# CH32F_V208W-R0.net
KiCad netlist of a schematic drawn in Altium Designer
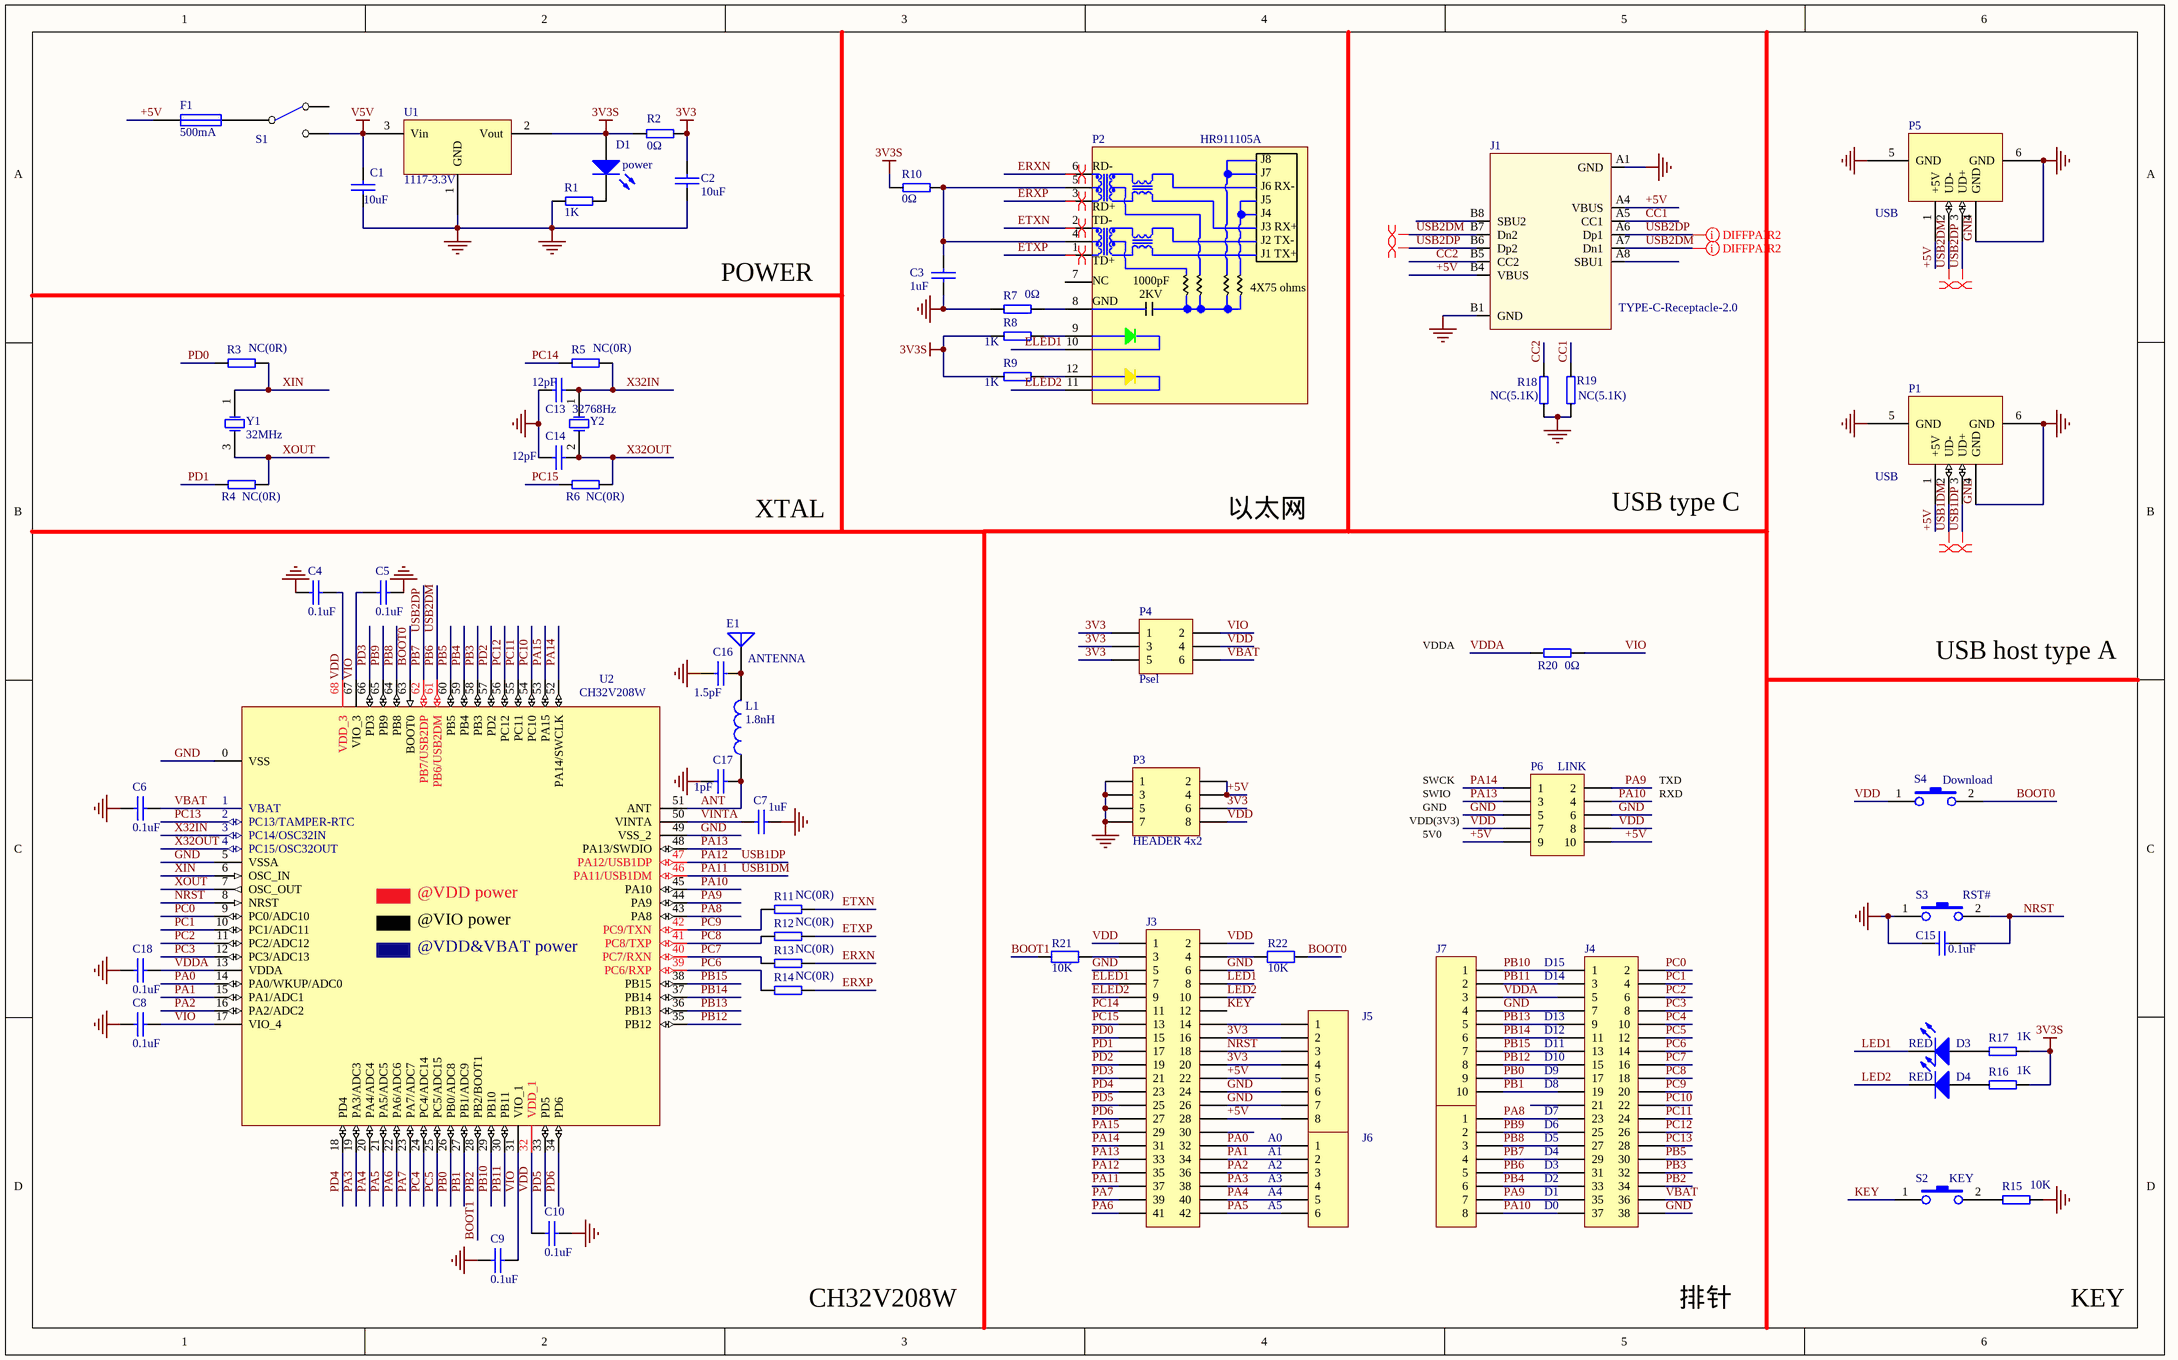
[diagram p0: CH32F&V208W-R0.SchDoc]

(export (version "E")
  (design (tool "Eeschema 10.0.6"))
  (components
    (comp (ref "C1")
      (value "10uF")
      (footprint "3216_C")
      (description "Capacitor")
      (libsource (lib "") (part "CAP_1"))
    )
    (comp (ref "C2")
      (value "10uF")
      (footprint "0603_C")
      (description "Capacitor")
      (libsource (lib "") (part "CAP_1"))
    )
    (comp (ref "C3")
      (value "1uF")
      (footprint "0603_C")
      (description "Capacitor")
      (libsource (lib "") (part "CAP_1"))
    )
    (comp (ref "C4")
      (value "0.1uF")
      (footprint "0603_C")
      (description "Capacitor")
      (libsource (lib "*") (part "CAP"))
    )
    (comp (ref "C5")
      (value "0.1uF")
      (footprint "0603_C")
      (description "Capacitor")
      (libsource (lib "*") (part "CAP"))
    )
    (comp (ref "C6")
      (value "0.1uF")
      (footprint "0603_C")
      (description "Capacitor")
      (libsource (lib "*") (part "CAP"))
    )
    (comp (ref "C7")
      (value "1uF")
      (footprint "0603_C")
      (description "Capacitor")
      (libsource (lib "*") (part "CAP"))
    )
    (comp (ref "C8")
      (value "0.1uF")
      (footprint "0603_C")
      (description "Capacitor")
      (libsource (lib "*") (part "CAP"))
    )
    (comp (ref "C9")
      (value "0.1uF")
      (footprint "0603_C")
      (description "Capacitor")
      (libsource (lib "*") (part "CAP"))
    )
    (comp (ref "C10")
      (value "0.1uF")
      (footprint "0603_C")
      (description "Capacitor")
      (libsource (lib "*") (part "CAP"))
    )
    (comp (ref "C13")
      (value "12pF")
      (footprint "0603_C")
      (description "Capacitor")
      (libsource (lib "") (part "CAP_1"))
    )
    (comp (ref "C14")
      (value "12pF")
      (footprint "0603_C")
      (description "Capacitor")
      (libsource (lib "") (part "CAP_1"))
    )
    (comp (ref "C15")
      (value "0.1uF")
      (footprint "0603_C")
      (description "Capacitor")
      (libsource (lib "*") (part "CAP"))
    )
    (comp (ref "C16")
      (value "1.5pF")
      (footprint "0603_C")
      (description "Capacitor")
      (libsource (lib "*") (part "CAP"))
    )
    (comp (ref "C17")
      (value "1pF")
      (footprint "0603_C")
      (description "Capacitor")
      (libsource (lib "*") (part "CAP"))
    )
    (comp (ref "C18")
      (value "0.1uF")
      (footprint "0603_C")
      (description "Capacitor")
      (libsource (lib "*") (part "CAP"))
    )
    (comp (ref "D1")
      (value "power")
      (footprint "0603+")
      (description "Typical INFRARED GaAs LED")
      (fields (field (name "PUBLISHER") "Altium Limited"))
      (libsource (lib "*") (part "LED0"))
    )
    (comp (ref "D3")
      (value "RED")
      (footprint "0603+")
      (description "Typical INFRARED GaAs LED")
      (fields (field (name "PUBLISHER") "Altium Limited"))
      (libsource (lib "*") (part "LED0"))
    )
    (comp (ref "D4")
      (value "RED")
      (footprint "0603+")
      (description "Typical INFRARED GaAs LED")
      (fields (field (name "PUBLISHER") "Altium Limited"))
      (libsource (lib "*") (part "LED0"))
    )
    (comp (ref "E1")
      (value "ANTENNA")
      (footprint "MYPCB:ANT-F-1-2.4G-1.6")
      (description "Generic Antenna")
      (libsource (lib "*") (part "ANTENNA"))
    )
    (comp (ref "F1")
      (value "500mA")
      (footprint "0603")
      (description "Fuse")
      (libsource (lib "wch_sch_others") (part "FUSE1"))
    )
    (comp (ref "J1")
      (value "TYPE-C-Receptacle-2.0")
      (footprint "TYPE-C-Receptacle-2.0")
      (description "Type-C USB2.0 母座")
      (libsource (lib "Miscellaneous SCH Lib") (part "TYPE-C-Receptacle-2.0"))
    )
    (comp (ref "J3")
      (value "Header 21X2")
      (footprint "IDC42-2.54mm")
      (description "Header, 21-Pin, Dual row")
      (fields (field (name "PUBLISHER") "Altium Limited"))
      (libsource (lib "PCB_Project") (part "Header 21X2"))
    )
    (comp (ref "J4")
      (value "Header 19X2")
      (footprint "IDC38-2.54mm")
      (description "Header, 19-Pin, Dual row")
      (fields (field (name "PUBLISHER") "Altium Limited"))
      (libsource (lib "Miscellaneous Connectors") (part "Header 19X2"))
    )
    (comp (ref "J5")
      (value "Header 8")
      (footprint "SIP8-2.54mm")
      (description "Header, 8-Pin")
      (fields (field (name "PUBLISHER") "Altium Limited"))
      (libsource (lib "Miscellaneous Connectors") (part "Header 8"))
    )
    (comp (ref "J6")
      (value "Header 6")
      (footprint "SIP6-2.54MM")
      (description "Header, 6-Pin")
      (fields (field (name "PUBLISHER") "Altium Limited"))
      (libsource (lib "Miscellaneous Connectors") (part "Header 6"))
    )
    (comp (ref "J7")
      (value "Header 10")
      (footprint "SIP10-2.54mm")
      (description "Header, 10-Pin")
      (fields (field (name "PUBLISHER") "Altium Limited"))
      (libsource (lib "Miscellaneous Connectors") (part "Header 10"))
    )
    (comp (ref "J8")
      (value "Header 8")
      (footprint "SIP8-2.54mm")
      (description "Header, 8-Pin")
      (fields (field (name "PUBLISHER") "Altium Limited"))
      (libsource (lib "") (part "Header 8_1"))
    )
    (comp (ref "L1") (value "1.8nH") (footprint "0603") (libsource (lib "*") (part "INDUCTOR")))
    (comp (ref "P1")
      (value "USB")
      (footprint "USBAF")
      (description "USB Port")
      (libsource (lib "*") (part "USB"))
    )
    (comp (ref "P2") (value "HR911105A") (footprint "HR911105A") (libsource (lib "*") (part "HR911105A")))
    (comp (ref "P3")
      (value "HEADER 4x2")
      (footprint "MYPCB:IDC8-2.54mm")
      (description "Header, 4-Pin, Dual row")
      (libsource (lib "wch_sch_others") (part "HEADER 4x2"))
    )
    (comp (ref "P4")
      (value "Psel")
      (footprint "IDC6-2.54mm")
      (description "Header, 3-Pin, Dual row, Right Angle")
      (fields (field (name "PUBLISHER") "Altium Limited"))
      (libsource (lib "Miscellaneous Connectors") (part "Header 3X2H"))
    )
    (comp (ref "P5")
      (value "USB")
      (footprint "USBAF")
      (description "USB Port")
      (libsource (lib "*") (part "USB"))
    )
    (comp (ref "P6")
      (value "LINK")
      (footprint "IDC10-2.54mm")
      (description "Header, 5-Pin, Dual row, Right Angle")
      (fields (field (name "PUBLISHER") "Altium Limited"))
      (libsource (lib "Miscellaneous Connectors") (part "Header 5X2H"))
    )
    (comp (ref "R1") (value "1K") (footprint "0603") (libsource (lib "wch_sch_others") (part "RES")))
    (comp (ref "R2") (value "0Ω") (footprint "0603") (libsource (lib "wch_sch_others") (part "RES")))
    (comp (ref "R3") (value "NC(0R)") (footprint "0603") (libsource (lib "wch_sch_others") (part "RES")))
    (comp (ref "R4") (value "NC(0R)") (footprint "0603") (libsource (lib "wch_sch_others") (part "RES")))
    (comp (ref "R5") (value "NC(0R)") (footprint "0603") (libsource (lib "wch_sch_others") (part "RES")))
    (comp (ref "R6") (value "NC(0R)") (footprint "0603") (libsource (lib "wch_sch_others") (part "RES")))
    (comp (ref "R7") (value "0Ω") (footprint "0603") (libsource (lib "wch_sch_others") (part "RES")))
    (comp (ref "R8") (value "1K") (footprint "0603") (libsource (lib "wch_sch_others") (part "RES")))
    (comp (ref "R9") (value "1K") (footprint "0603") (libsource (lib "wch_sch_others") (part "RES")))
    (comp (ref "R10") (value "0Ω") (footprint "0603") (libsource (lib "wch_sch_others") (part "RES")))
    (comp (ref "R11") (value "NC(0R)") (footprint "0603") (libsource (lib "wch_sch_others") (part "RES")))
    (comp (ref "R12") (value "NC(0R)") (footprint "0603") (libsource (lib "wch_sch_others") (part "RES")))
    (comp (ref "R13") (value "NC(0R)") (footprint "0603") (libsource (lib "wch_sch_others") (part "RES")))
    (comp (ref "R14") (value "NC(0R)") (footprint "0603") (libsource (lib "wch_sch_others") (part "RES")))
    (comp (ref "R15") (value "10K") (footprint "0603") (libsource (lib "wch_sch_others") (part "RES")))
    (comp (ref "R16") (value "1K") (footprint "0603") (libsource (lib "wch_sch_others") (part "RES")))
    (comp (ref "R17") (value "1K") (footprint "0603") (libsource (lib "wch_sch_others") (part "RES")))
    (comp (ref "R18") (value "NC(5.1K)") (footprint "0603") (libsource (lib "wch_sch_others") (part "RES")))
    (comp (ref "R19") (value "NC(5.1K)") (footprint "0603") (libsource (lib "wch_sch_others") (part "RES")))
    (comp (ref "R20") (value "0Ω") (footprint "0603") (libsource (lib "*") (part "R")))
    (comp (ref "R21")
      (value "10K")
      (footprint "0603")
      (description "Resistor")
      (libsource (lib "Miscellaneous Devices") (part "Res2"))
    )
    (comp (ref "R22")
      (value "10K")
      (footprint "0603")
      (description "Resistor")
      (libsource (lib "Miscellaneous Devices") (part "Res2"))
    )
    (comp (ref "S1") (value "SW SPDT") (footprint "KEY_B") (libsource (lib "*") (part "SW SPDT")))
    (comp (ref "S2")
      (value "KEY")
      (footprint "SMD_6.1x3.65x2.5mm-KEY")
      (libsource (lib "wch_sch_others") (part "KEY1"))
    )
    (comp (ref "S3")
      (value "RST#")
      (footprint "SMD_6.1x3.65x2.5mm-KEY")
      (libsource (lib "wch_sch_others") (part "KEY1"))
    )
    (comp (ref "S4")
      (value "Download")
      (footprint "SMD_6.1x3.65x2.5mm-KEY")
      (libsource (lib "wch_sch_others") (part "KEY1"))
    )
    (comp (ref "U1")
      (value "1117-3.3V")
      (footprint "SOT-223")
      (libsource (lib "wch_sch_others") (part "1117-3.3V"))
    )
    (comp (ref "U2")
      (value "CH32V208W")
      (footprint "QFN68_8x8")
      (description "RISC-V BLE5.3 MCU, 10M Ethernet, 2*USB, CAN")
      (libsource (lib "CHXXX") (part "CH32V208W"))
    )
    (comp (ref "Y1")
      (value "32MHz")
      (footprint "XT3225")
      (description "Crystal Oscillator")
      (fields (field (name "PUBLISHER") "Altium Limited"))
      (libsource (lib "*") (part "XTAL"))
    )
    (comp (ref "Y2")
      (value "32768Hz")
      (footprint "FC-135")
      (description "Crystal Oscillator")
      (fields (field (name "PUBLISHER") "Altium Limited"))
      (libsource (lib "") (part "XTAL_1"))
    )
  )
  (nets
    (net (code "1") (name "/+5V") (class "Default")
      (node (ref "F1") (pin "1") (pinfunction "1_1") (pintype "passive"))
      (node (ref "J1") (pin "A4") (pinfunction "VBUS_A4") (pintype "passive"))
      (node (ref "J1") (pin "B4") (pinfunction "VBUS_B4") (pintype "passive"))
      (node (ref "J3") (pin "22") (pinfunction "22_22") (pintype "passive"))
      (node (ref "J3") (pin "28") (pinfunction "28_28") (pintype "passive"))
      (node (ref "J5") (pin "5") (pinfunction "5_5") (pintype "passive"))
      (node (ref "J5") (pin "8") (pinfunction "8_8") (pintype "passive"))
      (node (ref "P1") (pin "1") (pinfunction "+5V_1") (pintype "power_in"))
      (node (ref "P3") (pin "2") (pinfunction "2_2") (pintype "passive"))
      (node (ref "P3") (pin "4") (pinfunction "4_4") (pintype "passive"))
      (node (ref "P5") (pin "1") (pinfunction "+5V_1") (pintype "power_in"))
      (node (ref "P6") (pin "10") (pinfunction "10_10") (pintype "passive"))
      (node (ref "P6") (pin "9") (pinfunction "9_9") (pintype "passive"))
    )
    (net (code "2") (name "/ANT") (class "Default")
      (node (ref "C17") (pin "2") (pinfunction "2_2") (pintype "passive"))
      (node (ref "L1") (pin "1") (pinfunction "1_1") (pintype "passive"))
      (node (ref "U2") (pin "51") (pinfunction "ANT_51") (pintype "power_in"))
    )
    (net (code "3") (name "/BOOT0") (class "Default")
      (node (ref "R22") (pin "2") (pinfunction "2_2") (pintype "passive"))
      (node (ref "S4") (pin "2") (pinfunction "2_2") (pintype "passive"))
      (node (ref "U2") (pin "63") (pinfunction "BOOT0_63") (pintype "input"))
    )
    (net (code "4") (name "/BOOT1") (class "Default")
      (node (ref "J4") (pin "34") (pinfunction "34_34") (pintype "passive"))
      (node (ref "R21") (pin "1") (pinfunction "1_1") (pintype "passive"))
      (node (ref "U2") (pin "28") (pinfunction "PB2/BOOT1_28") (pintype "bidirectional"))
    )
    (net (code "5") (name "/CC1") (class "Default")
      (node (ref "J1") (pin "A5") (pinfunction "CC1_A5") (pintype "passive"))
      (node (ref "R19") (pin "1") (pintype "passive"))
    )
    (net (code "6") (name "/CC2") (class "Default")
      (node (ref "J1") (pin "B5") (pinfunction "CC2_B5") (pintype "passive"))
      (node (ref "R18") (pin "1") (pintype "passive"))
    )
    (net (code "7") (name "/ELED1") (class "Default")
      (node (ref "J3") (pin "7") (pinfunction "7_7") (pintype "passive"))
      (node (ref "P2") (pin "10") (pintype "passive"))
    )
    (net (code "8") (name "/ELED2") (class "Default")
      (node (ref "J3") (pin "9") (pinfunction "9_9") (pintype "passive"))
      (node (ref "P2") (pin "11") (pintype "passive"))
    )
    (net (code "9") (name "/ERXN") (class "Default")
      (node (ref "P2") (pin "6") (pintype "passive"))
      (node (ref "R13") (pin "2") (pintype "passive"))
    )
    (net (code "10") (name "/ERXP") (class "Default")
      (node (ref "P2") (pin "3") (pintype "passive"))
      (node (ref "R14") (pin "2") (pintype "passive"))
    )
    (net (code "11") (name "/ETXN") (class "Default")
      (node (ref "P2") (pin "2") (pintype "passive"))
      (node (ref "R11") (pin "2") (pintype "passive"))
    )
    (net (code "12") (name "/ETXP") (class "Default")
      (node (ref "P2") (pin "1") (pintype "passive"))
      (node (ref "R12") (pin "2") (pintype "passive"))
    )
    (net (code "13") (name "/KEY") (class "Default")
      (node (ref "J3") (pin "12") (pinfunction "12_12") (pintype "passive"))
      (node (ref "S2") (pin "1") (pinfunction "1_1") (pintype "passive"))
    )
    (net (code "14") (name "/LED1") (class "Default")
      (node (ref "D3") (pin "2") (pinfunction "K_2") (pintype "passive"))
      (node (ref "J3") (pin "8") (pinfunction "8_8") (pintype "passive"))
    )
    (net (code "15") (name "/LED2") (class "Default")
      (node (ref "D4") (pin "2") (pinfunction "K_2") (pintype "passive"))
      (node (ref "J3") (pin "10") (pinfunction "10_10") (pintype "passive"))
    )
    (net (code "16") (name "/NRST") (class "Default")
      (node (ref "C15") (pin "2") (pinfunction "2_2") (pintype "passive"))
      (node (ref "J3") (pin "18") (pinfunction "18_18") (pintype "passive"))
      (node (ref "J5") (pin "3") (pinfunction "3_3") (pintype "passive"))
      (node (ref "S3") (pin "2") (pinfunction "2_2") (pintype "passive"))
      (node (ref "U2") (pin "8") (pinfunction "NRST_8") (pintype "input"))
    )
    (net (code "17") (name "/PA0") (class "Default")
      (node (ref "J3") (pin "32") (pinfunction "32_32") (pintype "passive"))
      (node (ref "J6") (pin "1") (pinfunction "1_1") (pintype "passive"))
      (node (ref "U2") (pin "14") (pinfunction "PA0/WKUP/ADC0_14") (pintype "bidirectional"))
    )
    (net (code "18") (name "/PA1") (class "Default")
      (node (ref "J3") (pin "34") (pinfunction "34_34") (pintype "passive"))
      (node (ref "J6") (pin "2") (pinfunction "2_2") (pintype "passive"))
      (node (ref "U2") (pin "15") (pinfunction "PA1/ADC1_15") (pintype "bidirectional"))
    )
    (net (code "19") (name "/PA2") (class "Default")
      (node (ref "J3") (pin "36") (pinfunction "36_36") (pintype "passive"))
      (node (ref "J6") (pin "3") (pinfunction "3_3") (pintype "passive"))
      (node (ref "U2") (pin "16") (pinfunction "PA2/ADC2_16") (pintype "bidirectional"))
    )
    (net (code "20") (name "/PA3") (class "Default")
      (node (ref "J3") (pin "38") (pinfunction "38_38") (pintype "passive"))
      (node (ref "J6") (pin "4") (pinfunction "4_4") (pintype "passive"))
      (node (ref "U2") (pin "19") (pinfunction "PA3/ADC3_19") (pintype "bidirectional"))
    )
    (net (code "21") (name "/PA4") (class "Default")
      (node (ref "J3") (pin "40") (pinfunction "40_40") (pintype "passive"))
      (node (ref "J6") (pin "5") (pinfunction "5_5") (pintype "passive"))
      (node (ref "U2") (pin "20") (pinfunction "PA4/ADC4_20") (pintype "bidirectional"))
    )
    (net (code "22") (name "/PA5") (class "Default")
      (node (ref "J3") (pin "42") (pinfunction "42_42") (pintype "passive"))
      (node (ref "J6") (pin "6") (pinfunction "6_6") (pintype "passive"))
      (node (ref "U2") (pin "21") (pinfunction "PA5/ADC5_21") (pintype "bidirectional"))
    )
    (net (code "23") (name "/PA6") (class "Default")
      (node (ref "J3") (pin "41") (pinfunction "41_41") (pintype "passive"))
      (node (ref "U2") (pin "22") (pinfunction "PA6/ADC6_22") (pintype "bidirectional"))
    )
    (net (code "24") (name "/PA7") (class "Default")
      (node (ref "J3") (pin "39") (pinfunction "39_39") (pintype "passive"))
      (node (ref "U2") (pin "23") (pinfunction "PA7/ADC7_23") (pintype "bidirectional"))
    )
    (net (code "25") (name "/PA8") (class "Default")
      (node (ref "J4") (pin "23") (pinfunction "23_23") (pintype "passive"))
      (node (ref "J8") (pin "1") (pinfunction "1_1") (pintype "passive"))
      (node (ref "U2") (pin "43") (pinfunction "PA8_43") (pintype "bidirectional"))
    )
    (net (code "26") (name "/PA9") (class "Default")
      (node (ref "J4") (pin "35") (pinfunction "35_35") (pintype "passive"))
      (node (ref "J8") (pin "7") (pinfunction "7_7") (pintype "passive"))
      (node (ref "P6") (pin "2") (pinfunction "2_2") (pintype "passive"))
      (node (ref "U2") (pin "44") (pinfunction "PA9_44") (pintype "bidirectional"))
    )
    (net (code "27") (name "/PA10") (class "Default")
      (node (ref "J4") (pin "37") (pinfunction "37_37") (pintype "passive"))
      (node (ref "J8") (pin "8") (pinfunction "8_8") (pintype "passive"))
      (node (ref "P6") (pin "4") (pinfunction "4_4") (pintype "passive"))
      (node (ref "U2") (pin "45") (pinfunction "PA10_45") (pintype "bidirectional"))
    )
    (net (code "28") (name "/PA11") (class "Default")
      (node (ref "J3") (pin "37") (pinfunction "37_37") (pintype "passive"))
      (node (ref "P1") (pin "2") (pinfunction "UD-_2") (pintype "bidirectional"))
      (node (ref "U2") (pin "46") (pinfunction "PA11/USB1DM_46") (pintype "bidirectional"))
    )
    (net (code "29") (name "/PA12") (class "Default")
      (node (ref "J3") (pin "35") (pinfunction "35_35") (pintype "passive"))
      (node (ref "P1") (pin "3") (pinfunction "UD+_3") (pintype "bidirectional"))
      (node (ref "U2") (pin "47") (pinfunction "PA12/USB1DP_47") (pintype "bidirectional"))
    )
    (net (code "30") (name "/PA13") (class "Default")
      (node (ref "J3") (pin "33") (pinfunction "33_33") (pintype "passive"))
      (node (ref "P6") (pin "3") (pinfunction "3_3") (pintype "passive"))
      (node (ref "U2") (pin "48") (pinfunction "PA13/SWDIO_48") (pintype "bidirectional"))
    )
    (net (code "31") (name "/PA14") (class "Default")
      (node (ref "J3") (pin "31") (pinfunction "31_31") (pintype "passive"))
      (node (ref "P6") (pin "1") (pinfunction "1_1") (pintype "passive"))
      (node (ref "U2") (pin "52") (pinfunction "PA14/SWCLK_52") (pintype "bidirectional"))
    )
    (net (code "32") (name "/PA15") (class "Default")
      (node (ref "J3") (pin "29") (pinfunction "29_29") (pintype "passive"))
      (node (ref "U2") (pin "53") (pinfunction "PA15_53") (pintype "bidirectional"))
    )
    (net (code "33") (name "/PB0") (class "Default")
      (node (ref "J4") (pin "17") (pinfunction "17_17") (pintype "passive"))
      (node (ref "J7") (pin "9") (pinfunction "9_9") (pintype "passive"))
      (node (ref "U2") (pin "26") (pinfunction "PB0/ADC8_26") (pintype "bidirectional"))
    )
    (net (code "34") (name "/PB1") (class "Default")
      (node (ref "J4") (pin "19") (pinfunction "19_19") (pintype "passive"))
      (node (ref "J7") (pin "10") (pinfunction "10_10") (pintype "passive"))
      (node (ref "U2") (pin "27") (pinfunction "PB1/ADC9_27") (pintype "bidirectional"))
    )
    (net (code "35") (name "/PB3") (class "Default")
      (node (ref "J4") (pin "32") (pinfunction "32_32") (pintype "passive"))
      (node (ref "U2") (pin "58") (pinfunction "PB3_58") (pintype "bidirectional"))
    )
    (net (code "36") (name "/PB4") (class "Default")
      (node (ref "J4") (pin "33") (pinfunction "33_33") (pintype "passive"))
      (node (ref "J8") (pin "6") (pinfunction "6_6") (pintype "passive"))
      (node (ref "U2") (pin "59") (pinfunction "PB4_59") (pintype "bidirectional"))
    )
    (net (code "37") (name "/PB5") (class "Default")
      (node (ref "J4") (pin "30") (pinfunction "30_30") (pintype "passive"))
      (node (ref "U2") (pin "60") (pinfunction "PB5_60") (pintype "bidirectional"))
    )
    (net (code "38") (name "/PB6") (class "Default")
      (node (ref "J1") (pin "A7") (pinfunction "Dn1_A7") (pintype "passive"))
      (node (ref "J1") (pin "B7") (pinfunction "Dn2_B7") (pintype "passive"))
      (node (ref "J4") (pin "31") (pinfunction "31_31") (pintype "passive"))
      (node (ref "J8") (pin "5") (pinfunction "5_5") (pintype "passive"))
      (node (ref "P5") (pin "2") (pinfunction "UD-_2") (pintype "bidirectional"))
      (node (ref "U2") (pin "61") (pinfunction "PB6/USB2DM_61") (pintype "bidirectional"))
    )
    (net (code "39") (name "/PB7") (class "Default")
      (node (ref "J1") (pin "A6") (pinfunction "Dp1_A6") (pintype "passive"))
      (node (ref "J1") (pin "B6") (pinfunction "Dp2_B6") (pintype "passive"))
      (node (ref "J4") (pin "29") (pinfunction "29_29") (pintype "passive"))
      (node (ref "J8") (pin "4") (pinfunction "4_4") (pintype "passive"))
      (node (ref "P5") (pin "3") (pinfunction "UD+_3") (pintype "bidirectional"))
      (node (ref "U2") (pin "62") (pinfunction "PB7/USB2DP_62") (pintype "bidirectional"))
    )
    (net (code "40") (name "/PB8") (class "Default")
      (node (ref "J4") (pin "27") (pinfunction "27_27") (pintype "passive"))
      (node (ref "J8") (pin "3") (pinfunction "3_3") (pintype "passive"))
      (node (ref "U2") (pin "64") (pinfunction "PB8_64") (pintype "bidirectional"))
    )
    (net (code "41") (name "/PB9") (class "Default")
      (node (ref "J4") (pin "25") (pinfunction "25_25") (pintype "passive"))
      (node (ref "J8") (pin "2") (pinfunction "2_2") (pintype "passive"))
      (node (ref "U2") (pin "65") (pinfunction "PB9_65") (pintype "bidirectional"))
    )
    (net (code "42") (name "/PB10") (class "Default")
      (node (ref "J4") (pin "1") (pinfunction "1_1") (pintype "passive"))
      (node (ref "J7") (pin "1") (pinfunction "1_1") (pintype "passive"))
      (node (ref "U2") (pin "29") (pinfunction "PB10_29") (pintype "bidirectional"))
    )
    (net (code "43") (name "/PB11") (class "Default")
      (node (ref "J4") (pin "3") (pinfunction "3_3") (pintype "passive"))
      (node (ref "J7") (pin "2") (pinfunction "2_2") (pintype "passive"))
      (node (ref "U2") (pin "30") (pinfunction "PB11_30") (pintype "bidirectional"))
    )
    (net (code "44") (name "/PB12") (class "Default")
      (node (ref "J4") (pin "15") (pinfunction "15_15") (pintype "passive"))
      (node (ref "J7") (pin "8") (pinfunction "8_8") (pintype "passive"))
      (node (ref "U2") (pin "35") (pinfunction "PB12_35") (pintype "bidirectional"))
    )
    (net (code "45") (name "/PB13") (class "Default")
      (node (ref "J4") (pin "9") (pinfunction "9_9") (pintype "passive"))
      (node (ref "J7") (pin "5") (pinfunction "5_5") (pintype "passive"))
      (node (ref "U2") (pin "36") (pinfunction "PB13_36") (pintype "bidirectional"))
    )
    (net (code "46") (name "/PB14") (class "Default")
      (node (ref "J4") (pin "11") (pinfunction "11_11") (pintype "passive"))
      (node (ref "J7") (pin "6") (pinfunction "6_6") (pintype "passive"))
      (node (ref "U2") (pin "37") (pinfunction "PB14_37") (pintype "bidirectional"))
    )
    (net (code "47") (name "/PB15") (class "Default")
      (node (ref "J4") (pin "13") (pinfunction "13_13") (pintype "passive"))
      (node (ref "J7") (pin "7") (pinfunction "7_7") (pintype "passive"))
      (node (ref "U2") (pin "38") (pinfunction "PB15_38") (pintype "bidirectional"))
    )
    (net (code "48") (name "/PC0") (class "Default")
      (node (ref "J4") (pin "2") (pinfunction "2_2") (pintype "passive"))
      (node (ref "U2") (pin "9") (pinfunction "PC0/ADC10_9") (pintype "bidirectional"))
    )
    (net (code "49") (name "/PC1") (class "Default")
      (node (ref "J4") (pin "4") (pinfunction "4_4") (pintype "passive"))
      (node (ref "U2") (pin "10") (pinfunction "PC1/ADC11_10") (pintype "bidirectional"))
    )
    (net (code "50") (name "/PC2") (class "Default")
      (node (ref "J4") (pin "6") (pinfunction "6_6") (pintype "passive"))
      (node (ref "U2") (pin "11") (pinfunction "PC2/ADC12_11") (pintype "bidirectional"))
    )
    (net (code "51") (name "/PC3") (class "Default")
      (node (ref "J4") (pin "8") (pinfunction "8_8") (pintype "passive"))
      (node (ref "U2") (pin "12") (pinfunction "PC3/ADC13_12") (pintype "bidirectional"))
    )
    (net (code "52") (name "/PC4") (class "Default")
      (node (ref "J4") (pin "10") (pinfunction "10_10") (pintype "passive"))
      (node (ref "U2") (pin "24") (pinfunction "PC4/ADC14_24") (pintype "bidirectional"))
    )
    (net (code "53") (name "/PC5") (class "Default")
      (node (ref "J4") (pin "12") (pinfunction "12_12") (pintype "passive"))
      (node (ref "U2") (pin "25") (pinfunction "PC5/ADC15_25") (pintype "bidirectional"))
    )
    (net (code "54") (name "/PC6") (class "Default")
      (node (ref "J4") (pin "14") (pinfunction "14_14") (pintype "passive"))
      (node (ref "R14") (pin "1") (pintype "passive"))
      (node (ref "U2") (pin "39") (pinfunction "PC6/RXP_39") (pintype "bidirectional"))
    )
    (net (code "55") (name "/PC7") (class "Default")
      (node (ref "J4") (pin "16") (pinfunction "16_16") (pintype "passive"))
      (node (ref "R13") (pin "1") (pintype "passive"))
      (node (ref "U2") (pin "40") (pinfunction "PC7/RXN_40") (pintype "bidirectional"))
    )
    (net (code "56") (name "/PC8") (class "Default")
      (node (ref "J4") (pin "18") (pinfunction "18_18") (pintype "passive"))
      (node (ref "R12") (pin "1") (pintype "passive"))
      (node (ref "U2") (pin "41") (pinfunction "PC8/TXP_41") (pintype "bidirectional"))
    )
    (net (code "57") (name "/PC9") (class "Default")
      (node (ref "J4") (pin "20") (pinfunction "20_20") (pintype "passive"))
      (node (ref "R11") (pin "1") (pintype "passive"))
      (node (ref "U2") (pin "42") (pinfunction "PC9/TXN_42") (pintype "bidirectional"))
    )
    (net (code "58") (name "/PC10") (class "Default")
      (node (ref "J4") (pin "22") (pinfunction "22_22") (pintype "passive"))
      (node (ref "U2") (pin "54") (pinfunction "PC10_54") (pintype "bidirectional"))
    )
    (net (code "59") (name "/PC11") (class "Default")
      (node (ref "J4") (pin "24") (pinfunction "24_24") (pintype "passive"))
      (node (ref "U2") (pin "55") (pinfunction "PC11_55") (pintype "bidirectional"))
    )
    (net (code "60") (name "/PC12") (class "Default")
      (node (ref "J4") (pin "26") (pinfunction "26_26") (pintype "passive"))
      (node (ref "U2") (pin "56") (pinfunction "PC12_56") (pintype "bidirectional"))
    )
    (net (code "61") (name "/PC13") (class "Default")
      (node (ref "J4") (pin "28") (pinfunction "28_28") (pintype "passive"))
      (node (ref "U2") (pin "2") (pinfunction "PC13/TAMPER-RTC_2") (pintype "bidirectional"))
    )
    (net (code "62") (name "/PC14") (class "Default")
      (node (ref "J3") (pin "11") (pinfunction "11_11") (pintype "passive"))
      (node (ref "R5") (pin "1") (pintype "passive"))
    )
    (net (code "63") (name "/PC15") (class "Default")
      (node (ref "J3") (pin "13") (pinfunction "13_13") (pintype "passive"))
      (node (ref "R6") (pin "1") (pintype "passive"))
    )
    (net (code "64") (name "/PD0") (class "Default")
      (node (ref "J3") (pin "15") (pinfunction "15_15") (pintype "passive"))
      (node (ref "R3") (pin "1") (pintype "passive"))
    )
    (net (code "65") (name "/PD1") (class "Default")
      (node (ref "J3") (pin "17") (pinfunction "17_17") (pintype "passive"))
      (node (ref "R4") (pin "1") (pintype "passive"))
    )
    (net (code "66") (name "/PD2") (class "Default")
      (node (ref "J3") (pin "19") (pinfunction "19_19") (pintype "passive"))
      (node (ref "U2") (pin "57") (pinfunction "PD2_57") (pintype "bidirectional"))
    )
    (net (code "67") (name "/PD3") (class "Default")
      (node (ref "J3") (pin "21") (pinfunction "21_21") (pintype "passive"))
      (node (ref "U2") (pin "66") (pinfunction "PD3_66") (pintype "bidirectional"))
    )
    (net (code "68") (name "/PD4") (class "Default")
      (node (ref "J3") (pin "23") (pinfunction "23_23") (pintype "passive"))
      (node (ref "U2") (pin "18") (pinfunction "PD4_18") (pintype "bidirectional"))
    )
    (net (code "69") (name "/PD5") (class "Default")
      (node (ref "J3") (pin "25") (pinfunction "25_25") (pintype "passive"))
      (node (ref "U2") (pin "33") (pinfunction "PD5_33") (pintype "bidirectional"))
    )
    (net (code "70") (name "/PD6") (class "Default")
      (node (ref "J3") (pin "27") (pinfunction "27_27") (pintype "passive"))
      (node (ref "U2") (pin "34") (pinfunction "PD6_34") (pintype "bidirectional"))
    )
    (net (code "71") (name "/VBAT") (class "Default")
      (node (ref "C6") (pin "1") (pinfunction "1_1") (pintype "passive"))
      (node (ref "J4") (pin "36") (pinfunction "36_36") (pintype "passive"))
      (node (ref "P4") (pin "6") (pinfunction "6_6") (pintype "passive"))
      (node (ref "U2") (pin "1") (pinfunction "VBAT_1") (pintype "power_in"))
    )
    (net (code "72") (name "/VDD") (class "Default")
      (node (ref "C10") (pin "2") (pinfunction "2_2") (pintype "passive"))
      (node (ref "C4") (pin "1") (pinfunction "1_1") (pintype "passive"))
      (node (ref "J3") (pin "1") (pinfunction "1_1") (pintype "passive"))
      (node (ref "J3") (pin "2") (pinfunction "2_2") (pintype "passive"))
      (node (ref "P3") (pin "8") (pinfunction "8_8") (pintype "passive"))
      (node (ref "P4") (pin "4") (pinfunction "4_4") (pintype "passive"))
      (node (ref "P6") (pin "7") (pinfunction "7_7") (pintype "passive"))
      (node (ref "P6") (pin "8") (pinfunction "8_8") (pintype "passive"))
      (node (ref "S4") (pin "1") (pinfunction "1_1") (pintype "passive"))
      (node (ref "U2") (pin "32") (pinfunction "VDD_1_32") (pintype "power_in"))
      (node (ref "U2") (pin "68") (pinfunction "VDD_3_68") (pintype "power_in"))
    )
    (net (code "73") (name "/VDDA") (class "Default")
      (node (ref "C18") (pin "1") (pinfunction "1_1") (pintype "passive"))
      (node (ref "J4") (pin "5") (pinfunction "5_5") (pintype "passive"))
      (node (ref "J7") (pin "3") (pinfunction "3_3") (pintype "passive"))
      (node (ref "R20") (pin "2") (pinfunction "2_2") (pintype "passive"))
      (node (ref "U2") (pin "13") (pinfunction "VDDA_13") (pintype "power_in"))
    )
    (net (code "74") (name "/VINTA") (class "Default")
      (node (ref "C7") (pin "1") (pinfunction "1_1") (pintype "passive"))
      (node (ref "U2") (pin "50") (pinfunction "VINTA_50") (pintype "power_in"))
    )
    (net (code "75") (name "/VIO") (class "Default")
      (node (ref "C5") (pin "2") (pinfunction "2_2") (pintype "passive"))
      (node (ref "C8") (pin "1") (pinfunction "1_1") (pintype "passive"))
      (node (ref "C9") (pin "1") (pinfunction "1_1") (pintype "passive"))
      (node (ref "P4") (pin "2") (pinfunction "2_2") (pintype "passive"))
      (node (ref "R20") (pin "1") (pinfunction "1_1") (pintype "passive"))
      (node (ref "U2") (pin "17") (pinfunction "VIO_4_17") (pintype "power_in"))
      (node (ref "U2") (pin "31") (pinfunction "VIO_1_31") (pintype "power_in"))
      (node (ref "U2") (pin "67") (pinfunction "VIO_3_67") (pintype "power_in"))
    )
    (net (code "76") (name "/X32IN") (class "Default")
      (node (ref "C13") (pin "2") (pinfunction "2_2") (pintype "passive"))
      (node (ref "R5") (pin "2") (pintype "passive"))
      (node (ref "U2") (pin "3") (pinfunction "PC14/OSC32IN_3") (pintype "bidirectional"))
      (node (ref "Y2") (pin "1") (pinfunction "OSC1_1") (pintype "passive"))
    )
    (net (code "77") (name "/X32OUT") (class "Default")
      (node (ref "C14") (pin "2") (pinfunction "2_2") (pintype "passive"))
      (node (ref "R6") (pin "2") (pintype "passive"))
      (node (ref "U2") (pin "4") (pinfunction "PC15/OSC32OUT_4") (pintype "bidirectional"))
      (node (ref "Y2") (pin "2") (pinfunction "OSC2_2") (pintype "passive"))
    )
    (net (code "78") (name "/XIN") (class "Default")
      (node (ref "R3") (pin "2") (pintype "passive"))
      (node (ref "U2") (pin "6") (pinfunction "OSC_IN_6") (pintype "input"))
      (node (ref "Y1") (pin "1") (pinfunction "OSC1_1") (pintype "passive"))
    )
    (net (code "79") (name "/XOUT") (class "Default")
      (node (ref "R4") (pin "2") (pintype "passive"))
      (node (ref "U2") (pin "7") (pinfunction "OSC_OUT_7") (pintype "output"))
      (node (ref "Y1") (pin "3") (pinfunction "OSC2_3") (pintype "passive"))
    )
    (net (code "80") (name "3V3") (class "Default")
      (node (ref "C2") (pin "1") (pinfunction "1_1") (pintype "passive"))
      (node (ref "J3") (pin "16") (pinfunction "16_16") (pintype "passive"))
      (node (ref "J3") (pin "20") (pinfunction "20_20") (pintype "passive"))
      (node (ref "J5") (pin "2") (pinfunction "2_2") (pintype "passive"))
      (node (ref "J5") (pin "4") (pinfunction "4_4") (pintype "passive"))
      (node (ref "P3") (pin "6") (pinfunction "6_6") (pintype "passive"))
      (node (ref "P4") (pin "1") (pinfunction "1_1") (pintype "passive"))
      (node (ref "P4") (pin "3") (pinfunction "3_3") (pintype "passive"))
      (node (ref "P4") (pin "5") (pinfunction "5_5") (pintype "passive"))
      (node (ref "R2") (pin "1") (pintype "passive"))
    )
    (net (code "81") (name "3V3S") (class "Default")
      (node (ref "D1") (pin "1") (pinfunction "A_1") (pintype "passive"))
      (node (ref "R10") (pin "2") (pintype "passive"))
      (node (ref "R16") (pin "1") (pintype "passive"))
      (node (ref "R17") (pin "1") (pintype "passive"))
      (node (ref "R2") (pin "2") (pintype "passive"))
      (node (ref "R8") (pin "1") (pintype "passive"))
      (node (ref "R9") (pin "1") (pintype "passive"))
      (node (ref "U1") (pin "2") (pinfunction "Vout_2") (pintype "passive"))
    )
    (net (code "82") (name "GND") (class "Default")
      (node (ref "C1") (pin "2") (pinfunction "2_2") (pintype "passive"))
      (node (ref "C10") (pin "1") (pinfunction "1_1") (pintype "passive"))
      (node (ref "C13") (pin "1") (pinfunction "1_1") (pintype "passive"))
      (node (ref "C14") (pin "1") (pinfunction "1_1") (pintype "passive"))
      (node (ref "C15") (pin "1") (pinfunction "1_1") (pintype "passive"))
      (node (ref "C16") (pin "1") (pinfunction "1_1") (pintype "passive"))
      (node (ref "C17") (pin "1") (pinfunction "1_1") (pintype "passive"))
      (node (ref "C18") (pin "2") (pinfunction "2_2") (pintype "passive"))
      (node (ref "C2") (pin "2") (pinfunction "2_2") (pintype "passive"))
      (node (ref "C3") (pin "1") (pinfunction "1_1") (pintype "passive"))
      (node (ref "C4") (pin "2") (pinfunction "2_2") (pintype "passive"))
      (node (ref "C5") (pin "1") (pinfunction "1_1") (pintype "passive"))
      (node (ref "C6") (pin "2") (pinfunction "2_2") (pintype "passive"))
      (node (ref "C7") (pin "2") (pinfunction "2_2") (pintype "passive"))
      (node (ref "C8") (pin "2") (pinfunction "2_2") (pintype "passive"))
      (node (ref "C9") (pin "2") (pinfunction "2_2") (pintype "passive"))
      (node (ref "J1") (pin "A1") (pinfunction "GND_A1") (pintype "passive"))
      (node (ref "J1") (pin "B1") (pinfunction "GND_B1") (pintype "passive"))
      (node (ref "J3") (pin "24") (pinfunction "24_24") (pintype "passive"))
      (node (ref "J3") (pin "26") (pinfunction "26_26") (pintype "passive"))
      (node (ref "J3") (pin "5") (pinfunction "5_5") (pintype "passive"))
      (node (ref "J3") (pin "6") (pinfunction "6_6") (pintype "passive"))
      (node (ref "J4") (pin "38") (pinfunction "38_38") (pintype "passive"))
      (node (ref "J4") (pin "7") (pinfunction "7_7") (pintype "passive"))
      (node (ref "J5") (pin "6") (pinfunction "6_6") (pintype "passive"))
      (node (ref "J5") (pin "7") (pinfunction "7_7") (pintype "passive"))
      (node (ref "J7") (pin "4") (pinfunction "4_4") (pintype "passive"))
      (node (ref "P1") (pin "4") (pinfunction "GND_4") (pintype "power_in"))
      (node (ref "P1") (pin "5") (pinfunction "GND_5") (pintype "power_in"))
      (node (ref "P1") (pin "6") (pinfunction "GND_6") (pintype "power_in"))
      (node (ref "P3") (pin "1") (pinfunction "1_1") (pintype "passive"))
      (node (ref "P3") (pin "3") (pinfunction "3_3") (pintype "passive"))
      (node (ref "P3") (pin "5") (pinfunction "5_5") (pintype "passive"))
      (node (ref "P3") (pin "7") (pinfunction "7_7") (pintype "passive"))
      (node (ref "P5") (pin "4") (pinfunction "GND_4") (pintype "power_in"))
      (node (ref "P5") (pin "5") (pinfunction "GND_5") (pintype "power_in"))
      (node (ref "P5") (pin "6") (pinfunction "GND_6") (pintype "power_in"))
      (node (ref "P6") (pin "5") (pinfunction "5_5") (pintype "passive"))
      (node (ref "P6") (pin "6") (pinfunction "6_6") (pintype "passive"))
      (node (ref "R1") (pin "1") (pintype "passive"))
      (node (ref "R15") (pin "1") (pintype "passive"))
      (node (ref "R18") (pin "2") (pintype "passive"))
      (node (ref "R19") (pin "2") (pintype "passive"))
      (node (ref "R7") (pin "1") (pintype "passive"))
      (node (ref "S3") (pin "1") (pinfunction "1_1") (pintype "passive"))
      (node (ref "U1") (pin "1") (pinfunction "GND_1") (pintype "passive"))
      (node (ref "U2") (pin "0") (pinfunction "VSS_0") (pintype "power_in"))
      (node (ref "U2") (pin "49") (pinfunction "VSS_2_49") (pintype "power_in"))
      (node (ref "U2") (pin "5") (pinfunction "VSSA_5") (pintype "power_in"))
    )
    (net (code "83") (name "Net-(C3-Pad2)") (class "Default")
      (node (ref "C3") (pin "2") (pinfunction "2_2") (pintype "passive"))
      (node (ref "P2") (pin "4") (pintype "passive"))
      (node (ref "P2") (pin "5") (pintype "passive"))
      (node (ref "R10") (pin "1") (pintype "passive"))
    )
    (net (code "84") (name "Net-(D1-K)") (class "Default")
      (node (ref "D1") (pin "2") (pinfunction "K_2") (pintype "passive"))
      (node (ref "R1") (pin "2") (pintype "passive"))
    )
    (net (code "85") (name "Net-(D3-A)") (class "Default")
      (node (ref "D3") (pin "1") (pinfunction "A_1") (pintype "passive"))
      (node (ref "R17") (pin "2") (pintype "passive"))
    )
    (net (code "86") (name "Net-(D4-A)") (class "Default")
      (node (ref "D4") (pin "1") (pinfunction "A_1") (pintype "passive"))
      (node (ref "R16") (pin "2") (pintype "passive"))
    )
    (net (code "87") (name "Net-(E1-A)") (class "Default")
      (node (ref "C16") (pin "2") (pinfunction "2_2") (pintype "passive"))
      (node (ref "E1") (pin "1") (pinfunction "A_1") (pintype "passive"))
      (node (ref "L1") (pin "2") (pinfunction "2_2") (pintype "passive"))
    )
    (net (code "88") (name "Net-(J3-Pad3)") (class "Default")
      (node (ref "J3") (pin "3") (pinfunction "3_3") (pintype "passive"))
      (node (ref "R21") (pin "2") (pinfunction "2_2") (pintype "passive"))
    )
    (net (code "89") (name "Net-(J3-Pad4)") (class "Default")
      (node (ref "J3") (pin "4") (pinfunction "4_4") (pintype "passive"))
      (node (ref "R22") (pin "1") (pinfunction "1_1") (pintype "passive"))
    )
    (net (code "90") (name "Net-(J3-Pad14)") (class "Default")
      (node (ref "J3") (pin "14") (pinfunction "14_14") (pintype "passive"))
      (node (ref "J5") (pin "1") (pinfunction "1_1") (pintype "passive"))
    )
    (net (code "91") (name "Net-(P2-Pad8)") (class "Default")
      (node (ref "P2") (pin "8") (pintype "passive"))
      (node (ref "R7") (pin "2") (pintype "passive"))
    )
    (net (code "92") (name "Net-(P2-Pad9)") (class "Default")
      (node (ref "P2") (pin "9") (pintype "passive"))
      (node (ref "R8") (pin "2") (pintype "passive"))
    )
    (net (code "93") (name "Net-(P2-Pad12)") (class "Default")
      (node (ref "P2") (pin "12") (pintype "passive"))
      (node (ref "R9") (pin "2") (pintype "passive"))
    )
    (net (code "94") (name "Net-(R15-Pad2)") (class "Default")
      (node (ref "R15") (pin "2") (pintype "passive"))
      (node (ref "S2") (pin "2") (pinfunction "2_2") (pintype "passive"))
    )
    (net (code "95") (name "Net-(S1-COMMON)") (class "Default")
      (node (ref "F1") (pin "2") (pinfunction "2_2") (pintype "passive"))
      (node (ref "S1") (pin "1") (pinfunction "COMMON_1") (pintype "passive"))
    )
    (net (code "96") (name "V5V") (class "Default")
      (node (ref "C1") (pin "1") (pinfunction "1_1") (pintype "passive"))
      (node (ref "S1") (pin "2") (pinfunction "NC_2") (pintype "passive"))
      (node (ref "U1") (pin "3") (pinfunction "Vin_3") (pintype "passive"))
    )
    (net (code "97") (name "unconnected-(J1-SBU1-PadA8)") (class "Default")
      (node (ref "J1") (pin "A8") (pinfunction "SBU1_A8") (pintype "passive"))
    )
    (net (code "98") (name "unconnected-(J1-SBU2-PadB8)") (class "Default")
      (node (ref "J1") (pin "B8") (pinfunction "SBU2_B8") (pintype "passive"))
    )
    (net (code "99") (name "unconnected-(J3-Pad30)") (class "Default")
      (node (ref "J3") (pin "30") (pinfunction "30_30") (pintype "passive"))
    )
    (net (code "100") (name "unconnected-(J4-Pad21)") (class "Default")
      (node (ref "J4") (pin "21") (pinfunction "21_21") (pintype "passive"))
    )
    (net (code "101") (name "unconnected-(P2-Pad7)") (class "Default")
      (node (ref "P2") (pin "7") (pintype "passive"))
    )
    (net (code "102") (name "unconnected-(S1-NO-Pad3)") (class "Default")
      (node (ref "S1") (pin "3") (pinfunction "NO_3") (pintype "passive"))
    )
  )
)
